# Input_Power.net
KiCad netlist of a schematic drawn in Altium Designer
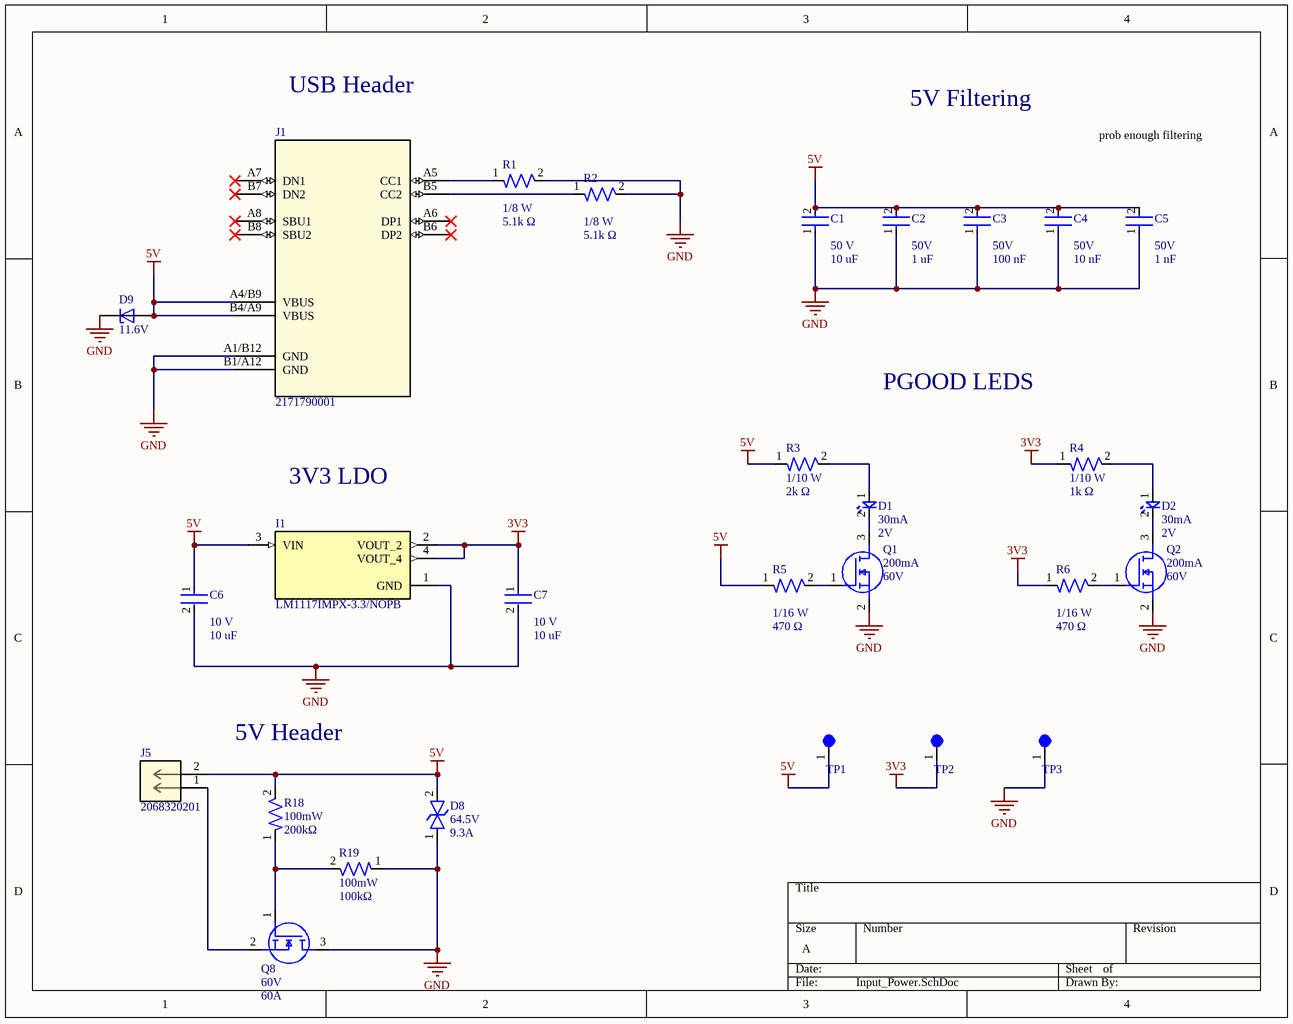
[diagram p0: Input_Power.SchDoc]

(export (version "E")
  (design (tool "Eeschema 10.0.6"))
  (components
    (comp (ref "C1")
      (value "CL32B106KBJNNWE")
      (footprint "CAP-1210")
      (fields (field (name "VOLTAGE RATING") "50 V") (field (name "CAPACITANCE") "10 uF"))
      (libsource (lib "EHW_27") (part "CAP 1210"))
    )
    (comp (ref "C2")
      (value "CC0805KKX7R9BB105")
      (footprint "CAP-0805")
      (fields (field (name "VOLTAGE RATING") "50V") (field (name "CAPACITANCE") "1 uF"))
      (libsource (lib "EHW_27") (part "CAP 0805"))
    )
    (comp (ref "C3")
      (value "CC0805KRX7R9BB104")
      (footprint "CAP-0805")
      (fields (field (name "VOLTAGE RATING") "50V") (field (name "CAPACITANCE") "100 nF"))
      (libsource (lib "EHW_27") (part "CAP 0805"))
    )
    (comp (ref "C4")
      (value "CC0603KPX7R9BB103")
      (footprint "CAP-0603")
      (fields (field (name "VOLTAGE RATING") "50V") (field (name "CAPACITANCE") "10 nF"))
      (libsource (lib "EHW_27") (part "CAP 0603"))
    )
    (comp (ref "C5")
      (value "CC0402KRX7R9BB102")
      (footprint "CAP-0402")
      (fields (field (name "VOLTAGE RATING") "50V") (field (name "CAPACITANCE") "1 nF"))
      (libsource (lib "EHW_27") (part "CAP 0402"))
    )
    (comp (ref "C6")
      (value "GRM188R61A106MAALJ")
      (footprint "CAP-0603")
      (fields (field (name "VOLTAGE RATING") "10 V") (field (name "CAPACITANCE") "10 uF"))
      (libsource (lib "EHW_27") (part "CAP 0603"))
    )
    (comp (ref "C7")
      (value "GRM188R61A106MAALJ")
      (footprint "CAP-0603")
      (fields (field (name "VOLTAGE RATING") "10 V") (field (name "CAPACITANCE") "10 uF"))
      (libsource (lib "EHW_27") (part "CAP 0603"))
    )
    (comp (ref "D1")
      (value "BL-HKC36G-AV-TRB")
      (footprint "LED-0603")
      (description "LED YELLOW CLEAR 0603 SMD")
      (fields (field (name "FORWARD CURRENT") "30mA") (field (name "FORWARD VOLTAGE") "2V"))
      (libsource (lib "EHW_27") (part "LED-0001"))
    )
    (comp (ref "D2")
      (value "BL-HKC36G-AV-TRB")
      (footprint "LED-0603")
      (description "LED YELLOW CLEAR 0603 SMD")
      (fields (field (name "FORWARD CURRENT") "30mA") (field (name "FORWARD VOLTAGE") "2V"))
      (libsource (lib "EHW_27") (part "LED-0001"))
    )
    (comp (ref "D8")
      (value "SMBJ5.0A")
      (footprint "DO-214AA (SMBJ)")
      (description "TVS DIODE 40VWM 64.5VC DO214AA")
      (fields (field (name "VOLTAGE RATING") "64.5V") (field (name "CURRENT RATING") "9.3A"))
      (libsource (lib "EHW_27") (part "DIO-TVS-0001"))
    )
    (comp (ref "D9")
      (value "ESDA7P60-1U1M")
      (footprint "TVS_ESDA7P60-1U1M")
      (description "TVS DIODE 5VWM 11.6VC 1610")
      (fields (field (name "MF") "{'manufacturer': u'STMicroelectronics'}") (field (name "VOLTAGE") "11.6V"))
      (libsource (lib "MasterLib") (part "DIO-TVS-11V"))
    )
    (comp (ref "I1")
      (value "LM1117IMPX-3.3/NOPB")
      (footprint "IC-SOT-223-4")
      (description "IC REG LIN 3.3V 800MA SOT223-4")
      (libsource (lib "EHW_27") (part "IC_LDO_3V3_0001"))
    )
    (comp (ref "J1")
      (value "2171790001")
      (footprint "2171790001_MOL")
      (fields (field (name "COPYRIGHT") "Copyright (C) 2025 Ultra Librarian. All rights reserved."))
      (libsource (lib "EHW_27") (part "2171790001"))
    )
    (comp (ref "J5")
      (value "2068320201")
      (footprint "CONN_2068320000-SD_02_MOL")
      (fields (field (name "COPYRIGHT") "Copyright (C) 2025 Ultra Librarian. All rights reserved."))
      (libsource (lib "EHW_27") (part "CONN MF+ 2 PIN VERT"))
    )
    (comp (ref "Q1")
      (value "T2N7002AK,LM")
      (footprint "IC-SOT23-3")
      (description "MOSFET N-CH 60V 200MA SOT23")
      (fields (field (name "CONTINUOUS CURRENT") "200mA") (field (name "VOLTAGE") "60V"))
      (libsource (lib "EHW_27") (part "NMOS-200MA-0001"))
    )
    (comp (ref "Q2")
      (value "T2N7002AK,LM")
      (footprint "IC-SOT23-3")
      (description "MOSFET N-CH 60V 200MA SOT23")
      (fields (field (name "CONTINUOUS CURRENT") "200mA") (field (name "VOLTAGE") "60V"))
      (libsource (lib "EHW_27") (part "NMOS-200MA-0001"))
    )
    (comp (ref "Q8")
      (value "CSD18543Q3AT")
      (footprint "IC-8VSONCLIP")
      (description "MOSFET N-CH 60V 12A/60A 8VSON")
      (fields (field (name "VOLTAGE") "60V") (field (name "CONTINUOUS CURRENT") "60A"))
      (libsource (lib "EHW_27") (part "NMOS-60A-0001"))
    )
    (comp (ref "R1")
      (value "RC0805JR-075K1L")
      (footprint "RES-0805")
      (fields (field (name "WATTAGE") "1/8 W") (field (name "RESISTANCE") "5.1k Ω"))
      (libsource (lib "EHW_27") (part "RES 0805"))
    )
    (comp (ref "R2")
      (value "RC0805JR-075K1L")
      (footprint "RES-0805")
      (fields (field (name "WATTAGE") "1/8 W") (field (name "RESISTANCE") "5.1k Ω"))
      (libsource (lib "EHW_27") (part "RES 0805"))
    )
    (comp (ref "R3")
      (value "RC0603FR-072KL")
      (footprint "RES-0603")
      (fields (field (name "WATTAGE") "1/10 W") (field (name "RESISTANCE") "2k Ω"))
      (libsource (lib "EHW_27") (part "RES 0603"))
    )
    (comp (ref "R4")
      (value "RT0603FRE131KL")
      (footprint "RES-0603")
      (fields (field (name "WATTAGE") "1/10 W") (field (name "RESISTANCE") "1k Ω"))
      (libsource (lib "EHW_27") (part "RES 0603"))
    )
    (comp (ref "R5")
      (value "RC0402FR-07470RL")
      (footprint "RES-0402")
      (fields (field (name "WATTAGE") "1/16 W") (field (name "RESISTANCE") "470 Ω"))
      (libsource (lib "EHW_27") (part "RES 0402"))
    )
    (comp (ref "R6")
      (value "RC0402FR-07470RL")
      (footprint "RES-0402")
      (fields (field (name "WATTAGE") "1/16 W") (field (name "RESISTANCE") "470 Ω"))
      (libsource (lib "EHW_27") (part "RES 0402"))
    )
    (comp (ref "R18")
      (value "RC0603FR-07200KL")
      (footprint "RES-0603")
      (fields (field (name "WATTAGE") "100mW") (field (name "RESISTANCE") "200kΩ"))
      (libsource (lib "EHW_27") (part "RES 0603"))
    )
    (comp (ref "R19")
      (value "RC0603FR-07100KL")
      (footprint "RES-0603")
      (fields (field (name "WATTAGE") "100mW") (field (name "RESISTANCE") "100kΩ"))
      (libsource (lib "EHW_27") (part "RES 0603"))
    )
    (comp (ref "TP1")
      (value "5003")
      (footprint "TEST-POINT-0001")
      (description "Oranange PC Test Point, Miniature Phoisphor Bronze Silver Plating Through Hole Mounting Type")
      (libsource (lib "EHW_27") (part "TEST-POINT-0001"))
    )
    (comp (ref "TP2")
      (value "5003")
      (footprint "TEST-POINT-0001")
      (description "Oranange PC Test Point, Miniature Phoisphor Bronze Silver Plating Through Hole Mounting Type")
      (libsource (lib "EHW_27") (part "TEST-POINT-0001"))
    )
    (comp (ref "TP3")
      (value "5003")
      (footprint "TEST-POINT-0001")
      (description "Oranange PC Test Point, Miniature Phoisphor Bronze Silver Plating Through Hole Mounting Type")
      (libsource (lib "EHW_27") (part "TEST-POINT-0001"))
    )
  )
  (nets
    (net (code "1") (name "3V3") (class "Default")
      (node (ref "C7") (pin "1") (pinfunction "1_1") (pintype "passive"))
      (node (ref "I1") (pin "2") (pinfunction "VOUT_2_2") (pintype "output"))
      (node (ref "I1") (pin "4") (pinfunction "VOUT_4_4") (pintype "output"))
      (node (ref "R4") (pin "1") (pinfunction "1_1") (pintype "passive"))
      (node (ref "R6") (pin "1") (pinfunction "1_1") (pintype "passive"))
      (node (ref "TP2") (pin "1") (pinfunction "0_1") (pintype "passive"))
    )
    (net (code "2") (name "5V") (class "Default")
      (node (ref "C1") (pin "2") (pinfunction "2_2") (pintype "passive"))
      (node (ref "C2") (pin "2") (pinfunction "2_2") (pintype "passive"))
      (node (ref "C3") (pin "2") (pinfunction "2_2") (pintype "passive"))
      (node (ref "C4") (pin "2") (pinfunction "2_2") (pintype "passive"))
      (node (ref "C5") (pin "2") (pinfunction "2_2") (pintype "passive"))
      (node (ref "C6") (pin "1") (pinfunction "1_1") (pintype "passive"))
      (node (ref "D8") (pin "2") (pintype "passive"))
      (node (ref "D9") (pin "2") (pinfunction "2_2") (pintype "passive"))
      (node (ref "I1") (pin "3") (pinfunction "VIN_3") (pintype "input"))
      (node (ref "J1") (pin "A4/B9") (pinfunction "VBUS_A4/B9") (pintype "power_in"))
      (node (ref "J1") (pin "B4/A9") (pinfunction "VBUS_B4/A9") (pintype "power_in"))
      (node (ref "J5") (pin "2") (pinfunction "2_2") (pintype "passive"))
      (node (ref "R18") (pin "2") (pinfunction "2_2") (pintype "passive"))
      (node (ref "R3") (pin "1") (pinfunction "1_1") (pintype "passive"))
      (node (ref "R5") (pin "1") (pinfunction "1_1") (pintype "passive"))
      (node (ref "TP1") (pin "1") (pinfunction "0_1") (pintype "passive"))
    )
    (net (code "3") (name "GND") (class "Default")
      (node (ref "C1") (pin "1") (pinfunction "1_1") (pintype "passive"))
      (node (ref "C2") (pin "1") (pinfunction "1_1") (pintype "passive"))
      (node (ref "C3") (pin "1") (pinfunction "1_1") (pintype "passive"))
      (node (ref "C4") (pin "1") (pinfunction "1_1") (pintype "passive"))
      (node (ref "C5") (pin "1") (pinfunction "1_1") (pintype "passive"))
      (node (ref "C6") (pin "2") (pinfunction "2_2") (pintype "passive"))
      (node (ref "C7") (pin "2") (pinfunction "2_2") (pintype "passive"))
      (node (ref "D8") (pin "1") (pintype "passive"))
      (node (ref "D9") (pin "1") (pinfunction "1_1") (pintype "passive"))
      (node (ref "I1") (pin "1") (pinfunction "GND_1") (pintype "power_in"))
      (node (ref "J1") (pin "A1/B12") (pinfunction "GND_A1/B12") (pintype "power_in"))
      (node (ref "J1") (pin "B1/A12") (pinfunction "GND_B1/A12") (pintype "power_in"))
      (node (ref "Q1") (pin "2") (pinfunction "S_2") (pintype "passive"))
      (node (ref "Q2") (pin "2") (pinfunction "S_2") (pintype "passive"))
      (node (ref "Q8") (pin "3") (pinfunction "D_3") (pintype "passive"))
      (node (ref "R1") (pin "2") (pinfunction "2_2") (pintype "passive"))
      (node (ref "R19") (pin "1") (pinfunction "1_1") (pintype "passive"))
      (node (ref "R2") (pin "2") (pinfunction "2_2") (pintype "passive"))
      (node (ref "TP3") (pin "1") (pinfunction "0_1") (pintype "passive"))
    )
    (net (code "4") (name "Net-(D1-Pad1)") (class "Default")
      (node (ref "D1") (pin "1") (pinfunction "1_1") (pintype "passive"))
      (node (ref "R3") (pin "2") (pinfunction "2_2") (pintype "passive"))
    )
    (net (code "5") (name "Net-(D2-Pad1)") (class "Default")
      (node (ref "D2") (pin "1") (pinfunction "1_1") (pintype "passive"))
      (node (ref "R4") (pin "2") (pinfunction "2_2") (pintype "passive"))
    )
    (net (code "6") (name "Net-(J1-CC1)") (class "Default")
      (node (ref "J1") (pin "A5") (pinfunction "CC1_A5") (pintype "bidirectional"))
      (node (ref "R1") (pin "1") (pinfunction "1_1") (pintype "passive"))
    )
    (net (code "7") (name "Net-(J1-CC2)") (class "Default")
      (node (ref "J1") (pin "B5") (pinfunction "CC2_B5") (pintype "bidirectional"))
      (node (ref "R2") (pin "1") (pinfunction "1_1") (pintype "passive"))
    )
    (net (code "8") (name "Net-(Q1-D)") (class "Default")
      (node (ref "D1") (pin "2") (pinfunction "2_2") (pintype "passive"))
      (node (ref "Q1") (pin "3") (pinfunction "D_3") (pintype "passive"))
    )
    (net (code "9") (name "Net-(Q1-G)") (class "Default")
      (node (ref "Q1") (pin "1") (pinfunction "G_1") (pintype "passive"))
      (node (ref "R5") (pin "2") (pinfunction "2_2") (pintype "passive"))
    )
    (net (code "10") (name "Net-(Q2-D)") (class "Default")
      (node (ref "D2") (pin "2") (pinfunction "2_2") (pintype "passive"))
      (node (ref "Q2") (pin "3") (pinfunction "D_3") (pintype "passive"))
    )
    (net (code "11") (name "Net-(Q2-G)") (class "Default")
      (node (ref "Q2") (pin "1") (pinfunction "G_1") (pintype "passive"))
      (node (ref "R6") (pin "2") (pinfunction "2_2") (pintype "passive"))
    )
    (net (code "12") (name "Net-(Q8-G)") (class "Default")
      (node (ref "Q8") (pin "1") (pinfunction "G_1") (pintype "passive"))
      (node (ref "R18") (pin "1") (pinfunction "1_1") (pintype "passive"))
      (node (ref "R19") (pin "2") (pinfunction "2_2") (pintype "passive"))
    )
    (net (code "13") (name "Net-(Q8-S)") (class "Default")
      (node (ref "J5") (pin "1") (pinfunction "1_1") (pintype "passive"))
      (node (ref "Q8") (pin "2") (pinfunction "S_2") (pintype "passive"))
    )
    (net (code "14") (name "unconnected-(J1-DN1-PadA7)") (class "Default")
      (node (ref "J1") (pin "A7") (pinfunction "DN1_A7") (pintype "bidirectional+no_connect"))
    )
    (net (code "15") (name "unconnected-(J1-DN2-PadB7)") (class "Default")
      (node (ref "J1") (pin "B7") (pinfunction "DN2_B7") (pintype "bidirectional+no_connect"))
    )
    (net (code "16") (name "unconnected-(J1-DP1-PadA6)") (class "Default")
      (node (ref "J1") (pin "A6") (pinfunction "DP1_A6") (pintype "bidirectional+no_connect"))
    )
    (net (code "17") (name "unconnected-(J1-DP2-PadB6)") (class "Default")
      (node (ref "J1") (pin "B6") (pinfunction "DP2_B6") (pintype "bidirectional+no_connect"))
    )
    (net (code "18") (name "unconnected-(J1-SBU1-PadA8)") (class "Default")
      (node (ref "J1") (pin "A8") (pinfunction "SBU1_A8") (pintype "bidirectional+no_connect"))
    )
    (net (code "19") (name "unconnected-(J1-SBU2-PadB8)") (class "Default")
      (node (ref "J1") (pin "B8") (pinfunction "SBU2_B8") (pintype "bidirectional+no_connect"))
    )
  )
)
